# Arduino-Esplora-06.net
KiCad netlist of a schematic drawn in EAGLE
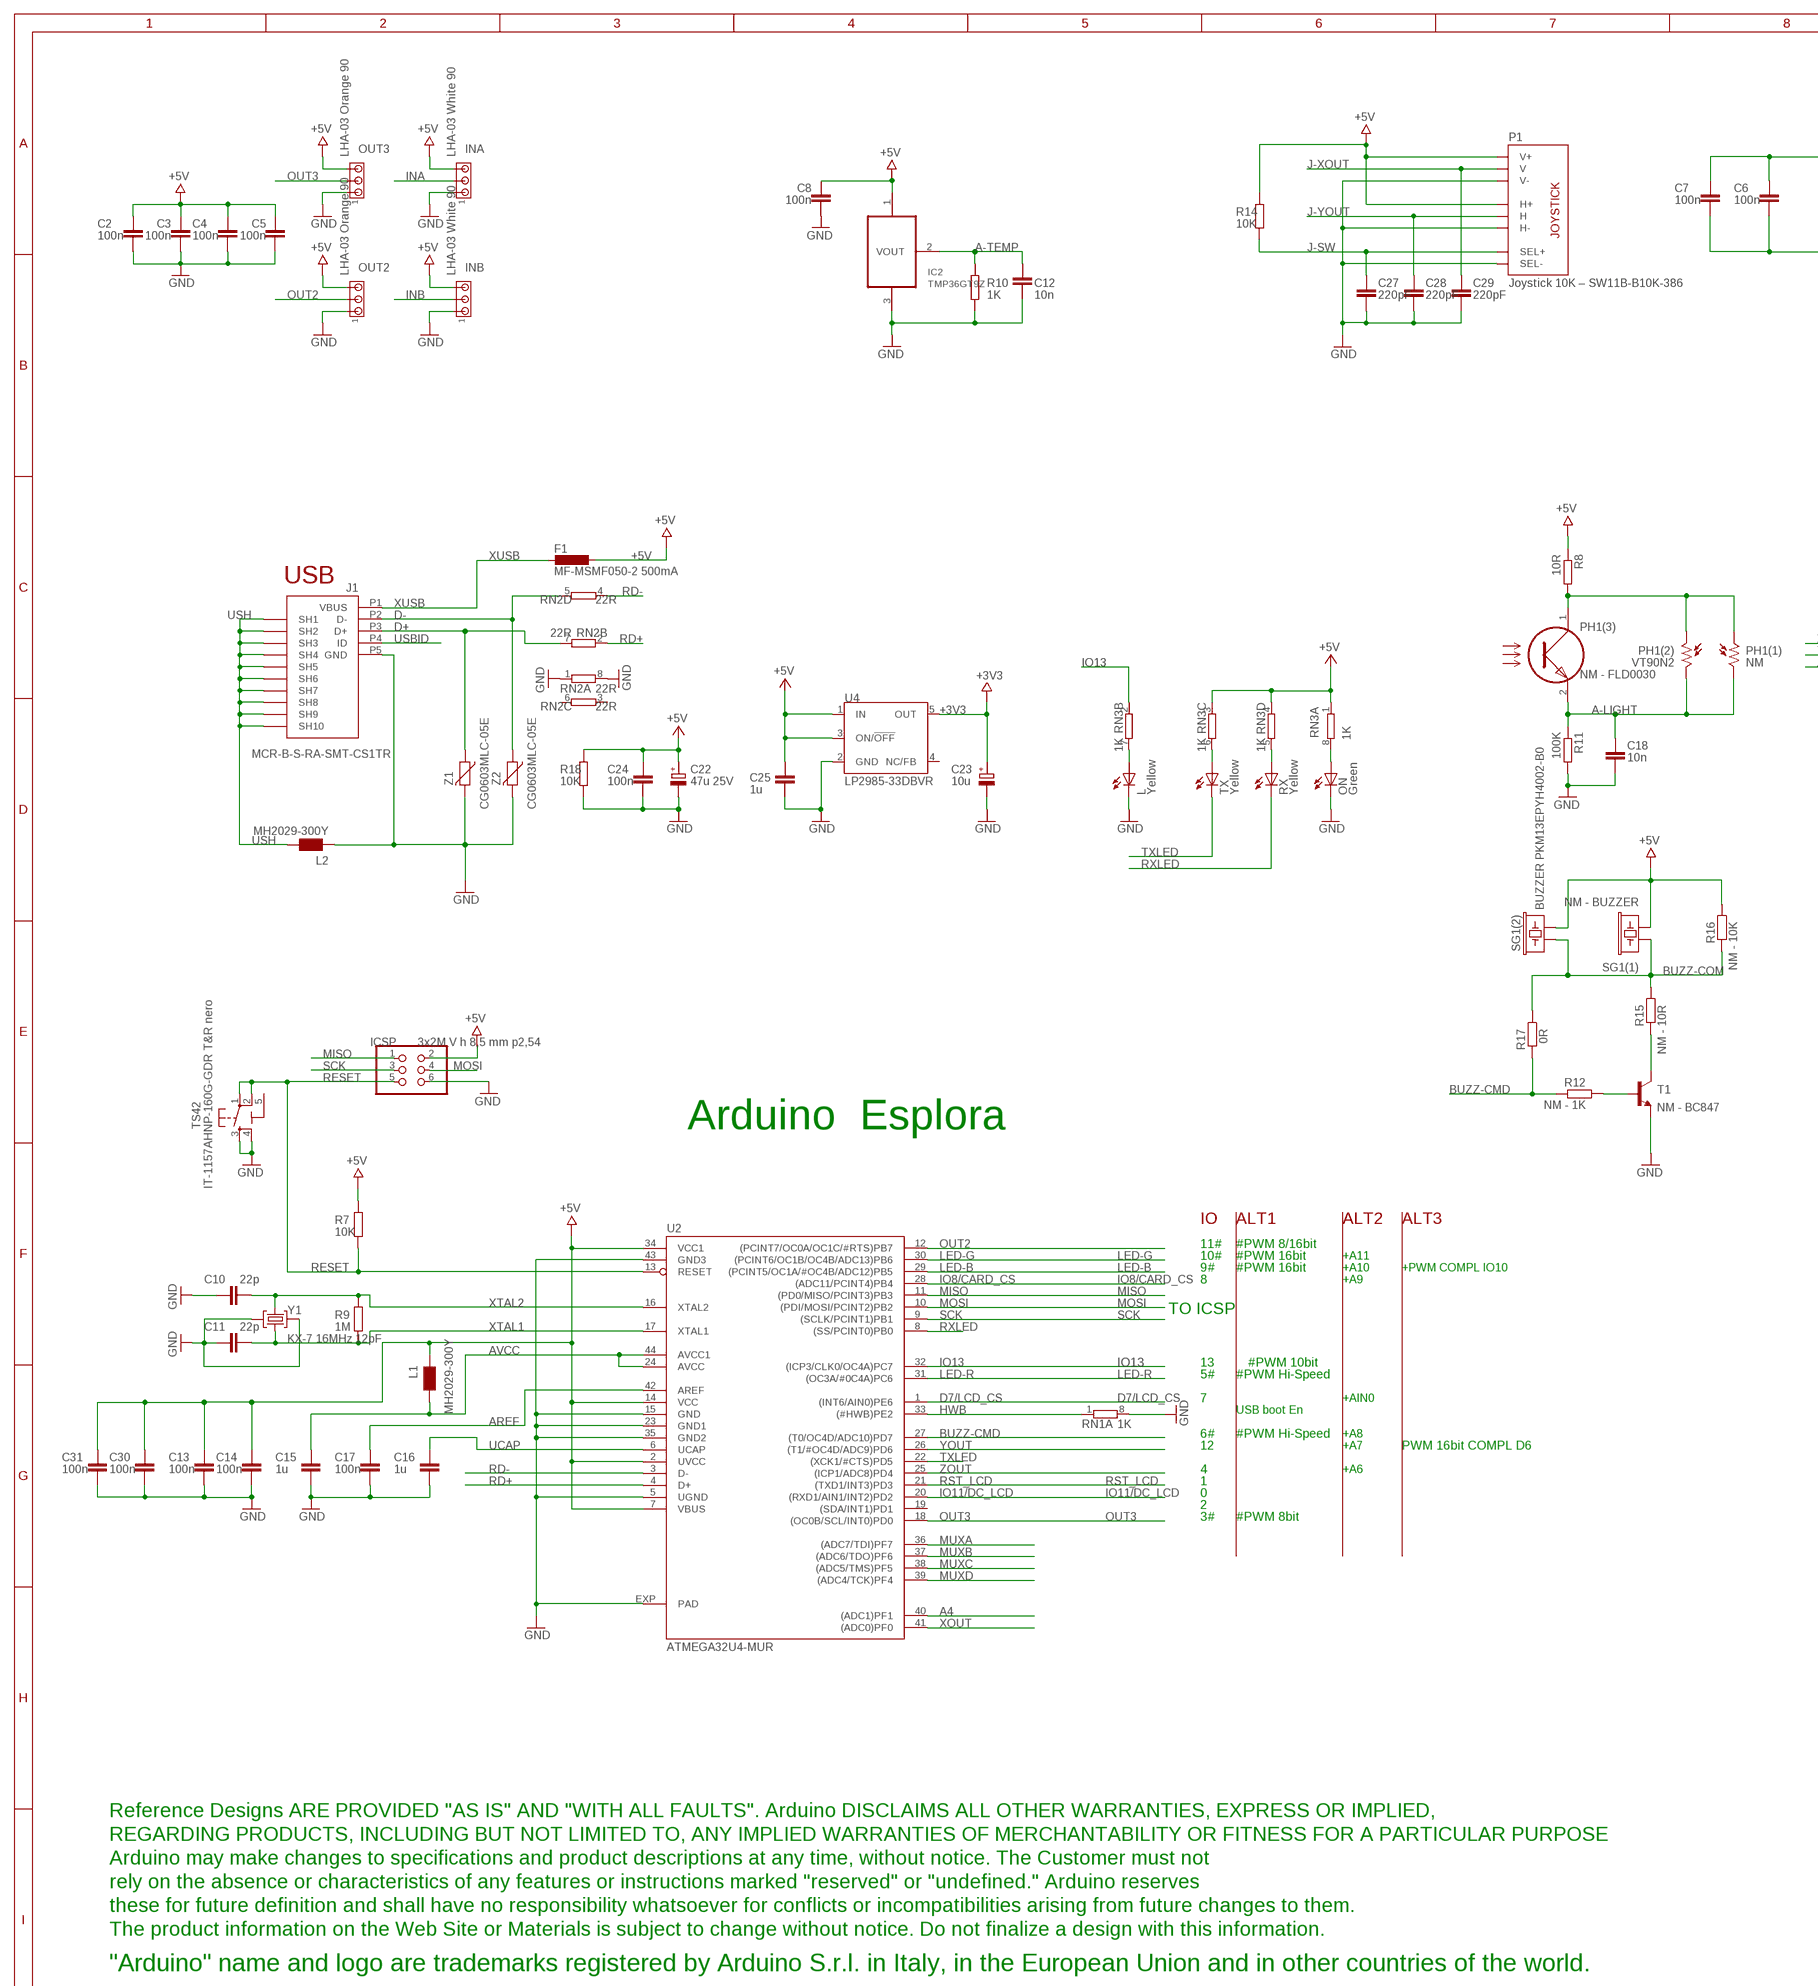
[diagram p0: schematic, sheet 1, part 1 of 2]
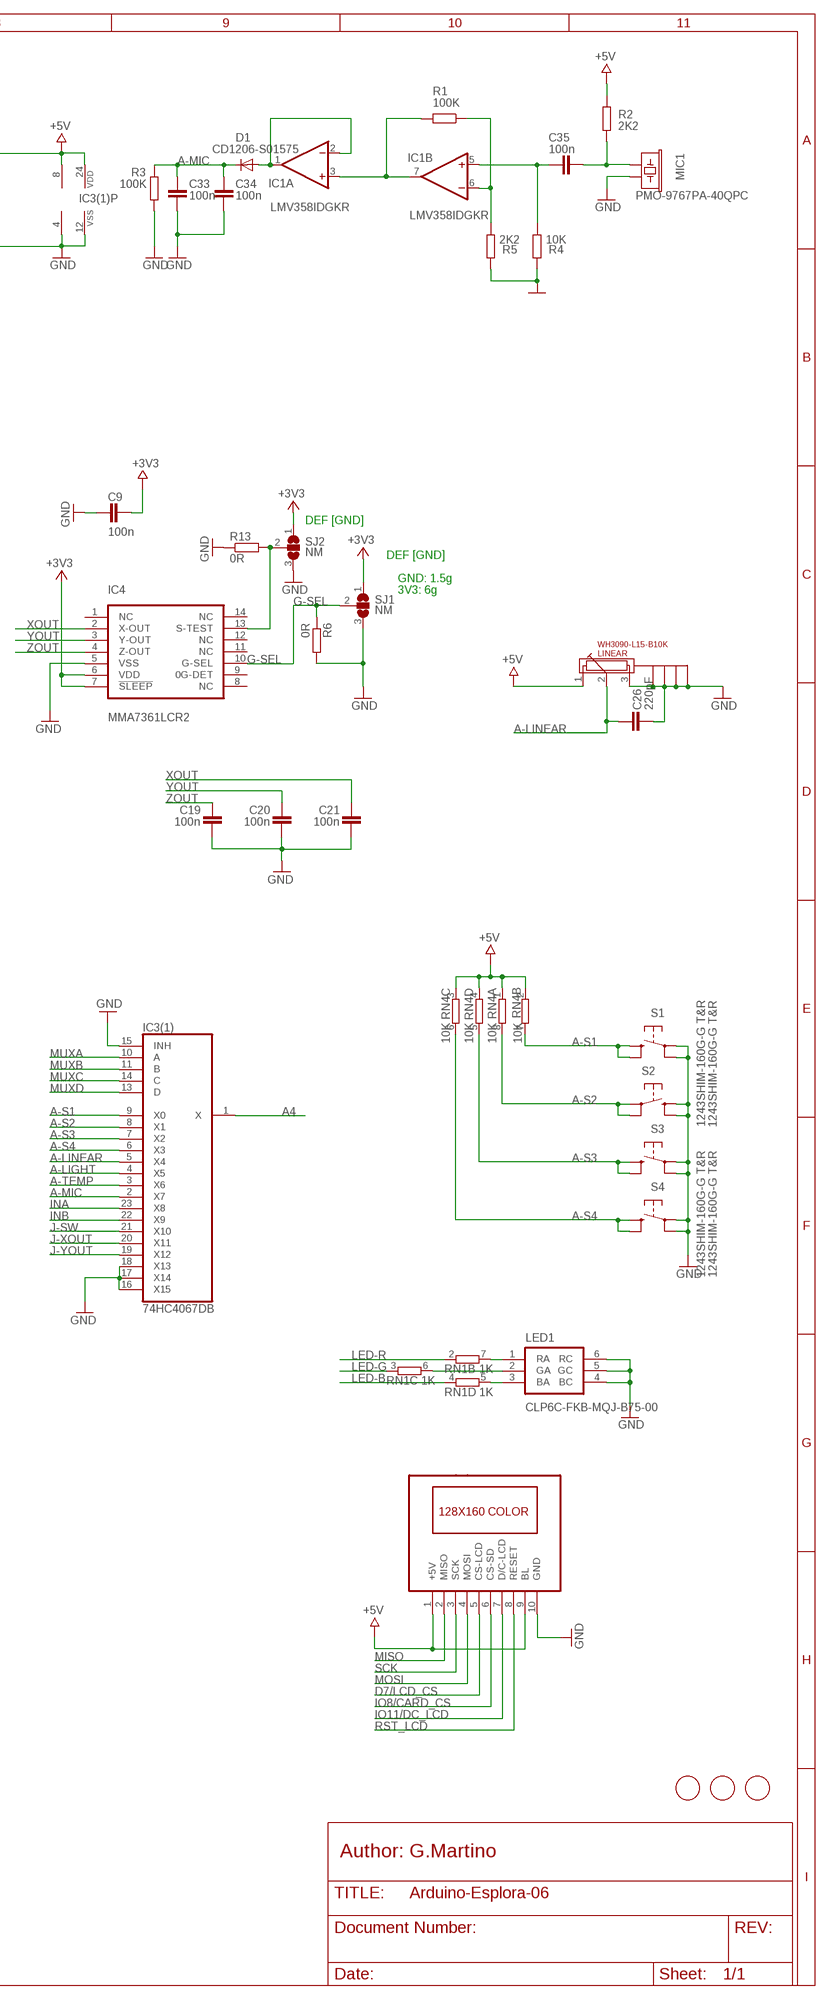
[diagram p1: schematic, sheet 1, part 2 of 2]

(export (version "E")
  (design (tool "Eeschema 10.0.6"))
  (components
    (comp (ref "C2")
      (value "100n")
      (footprint "eagle-import:C0603-ROUND")
      (libsource (lib "eagle-import") (part "C-EUC0603"))
    )
    (comp (ref "C3")
      (value "100n")
      (footprint "eagle-import:C0603-ROUND")
      (libsource (lib "eagle-import") (part "C-EUC0603"))
    )
    (comp (ref "C4")
      (value "100n")
      (footprint "eagle-import:C0603-ROUND")
      (libsource (lib "eagle-import") (part "C-EUC0603"))
    )
    (comp (ref "C5")
      (value "100n")
      (footprint "eagle-import:C0603-ROUND")
      (libsource (lib "eagle-import") (part "C-EUC0603"))
    )
    (comp (ref "C6")
      (value "100n")
      (footprint "eagle-import:C0603-ROUND")
      (libsource (lib "eagle-import") (part "C-EUC0603"))
    )
    (comp (ref "C7")
      (value "100n")
      (footprint "eagle-import:C0603-ROUND")
      (libsource (lib "eagle-import") (part "C-EUC0603"))
    )
    (comp (ref "C8")
      (value "100n")
      (footprint "eagle-import:C0603-ROUND")
      (libsource (lib "eagle-import") (part "C-EUC0603"))
    )
    (comp (ref "C9")
      (value "100n")
      (footprint "eagle-import:C0603-ROUND")
      (libsource (lib "eagle-import") (part "C-EUC0603"))
    )
    (comp (ref "C10")
      (value "22p")
      (footprint "eagle-import:C0603-ROUND")
      (libsource (lib "eagle-import") (part "C-EUC0603"))
    )
    (comp (ref "C11")
      (value "22p")
      (footprint "eagle-import:C0603-ROUND")
      (libsource (lib "eagle-import") (part "C-EUC0603"))
    )
    (comp (ref "C12")
      (value "10n")
      (footprint "eagle-import:C0603-ROUND")
      (libsource (lib "eagle-import") (part "C-EUC0603"))
    )
    (comp (ref "C13")
      (value "100n")
      (footprint "eagle-import:C0603-ROUND")
      (libsource (lib "eagle-import") (part "C-EUC0603"))
    )
    (comp (ref "C14")
      (value "100n")
      (footprint "eagle-import:C0603-ROUND")
      (libsource (lib "eagle-import") (part "C-EUC0603"))
    )
    (comp (ref "C15")
      (value "1u")
      (footprint "eagle-import:C0603-ROUND")
      (libsource (lib "eagle-import") (part "C-EUC0603"))
    )
    (comp (ref "C16")
      (value "1u")
      (footprint "eagle-import:C0603-ROUND")
      (libsource (lib "eagle-import") (part "C-EUC0603"))
    )
    (comp (ref "C17")
      (value "100n")
      (footprint "eagle-import:C0603-ROUND")
      (libsource (lib "eagle-import") (part "C-EUC0603"))
    )
    (comp (ref "C18")
      (value "10n")
      (footprint "eagle-import:C0603-ROUND")
      (libsource (lib "eagle-import") (part "C-EUC0603"))
    )
    (comp (ref "C19")
      (value "100n")
      (footprint "eagle-import:C0603-ROUND")
      (libsource (lib "eagle-import") (part "C-EUC0603"))
    )
    (comp (ref "C20")
      (value "100n")
      (footprint "eagle-import:C0603-ROUND")
      (libsource (lib "eagle-import") (part "C-EUC0603"))
    )
    (comp (ref "C21")
      (value "100n")
      (footprint "eagle-import:C0603-ROUND")
      (libsource (lib "eagle-import") (part "C-EUC0603"))
    )
    (comp (ref "C22")
      (value "47u 25V")
      (footprint "eagle-import:PANASONIC_D")
      (libsource (lib "eagle-import") (part "CPOL-EUD"))
    )
    (comp (ref "C23")
      (value "10u")
      (footprint "eagle-import:SMC_B")
      (libsource (lib "eagle-import") (part "CPOL-EUSMCB"))
    )
    (comp (ref "C24")
      (value "100n")
      (footprint "eagle-import:C0603-ROUND")
      (libsource (lib "eagle-import") (part "C-EUC0603"))
    )
    (comp (ref "C25")
      (value "1u")
      (footprint "eagle-import:C0603-ROUND")
      (libsource (lib "eagle-import") (part "C-EUC0603"))
    )
    (comp (ref "C26")
      (value "220pF")
      (footprint "eagle-import:C0603-ROUND")
      (libsource (lib "eagle-import") (part "C-EUC0603"))
    )
    (comp (ref "C27")
      (value "220pF")
      (footprint "eagle-import:C0603-ROUND")
      (libsource (lib "eagle-import") (part "C-EUC0603"))
    )
    (comp (ref "C28")
      (value "220pF")
      (footprint "eagle-import:C0603-ROUND")
      (libsource (lib "eagle-import") (part "C-EUC0603"))
    )
    (comp (ref "C29")
      (value "220pF")
      (footprint "eagle-import:C0603-ROUND")
      (libsource (lib "eagle-import") (part "C-EUC0603"))
    )
    (comp (ref "C30")
      (value "100n")
      (footprint "eagle-import:C0603-ROUND")
      (libsource (lib "eagle-import") (part "C-EUC0603"))
    )
    (comp (ref "C31")
      (value "100n")
      (footprint "eagle-import:C0603-ROUND")
      (libsource (lib "eagle-import") (part "C-EUC0603"))
    )
    (comp (ref "C33")
      (value "100n")
      (footprint "eagle-import:C0603-ROUND")
      (libsource (lib "eagle-import") (part "C-EUC0603"))
    )
    (comp (ref "C34")
      (value "100n")
      (footprint "eagle-import:C0603-ROUND")
      (libsource (lib "eagle-import") (part "C-EUC0603"))
    )
    (comp (ref "C35")
      (value "100n")
      (footprint "eagle-import:C0603-ROUND")
      (libsource (lib "eagle-import") (part "C-EUC0603"))
    )
    (comp (ref "D1")
      (value "CD1206-S01575")
      (footprint "eagle-import:MINIMELF")
      (libsource (lib "eagle-import") (part "DIODE-MINIMELF"))
    )
    (comp (ref "F1")
      (value "MF-MSMF050-2 500mA")
      (footprint "eagle-import:L1812")
      (libsource (lib "eagle-import") (part "L-EUL1812"))
    )
    (comp (ref "FID1")
      (value "FIDUCIALMOUNT")
      (footprint "eagle-import:FIDUCIA-MOUNT")
      (libsource (lib "eagle-import") (part "FIDUCIALMOUNT"))
    )
    (comp (ref "FID2")
      (value "FIDUCIALMOUNT")
      (footprint "eagle-import:FIDUCIA-MOUNT")
      (libsource (lib "eagle-import") (part "FIDUCIALMOUNT"))
    )
    (comp (ref "FID3")
      (value "FIDUCIALMOUNT")
      (footprint "eagle-import:FIDUCIA-MOUNT")
      (libsource (lib "eagle-import") (part "FIDUCIALMOUNT"))
    )
    (comp (ref "IC1")
      (value "LMV358IDGKR")
      (footprint "eagle-import:MSOP08")
      (libsource (lib "eagle-import") (part "LMV358?MMX"))
    )
    (comp (ref "IC2")
      (value "TMP36GT9Z")
      (footprint "eagle-import:TO92")
      (libsource (lib "eagle-import") (part "LM35TO-92"))
    )
    (comp (ref "IC3(1)")
      (value "74HC4067DB")
      (footprint "eagle-import:SSOP24(0.65)")
      (libsource (lib "eagle-import") (part "4067SM96"))
    )
    (comp (ref "IC4")
      (value "MMA7361LCR2")
      (footprint "eagle-import:LGA-14_3X5_0.8")
      (libsource (lib "eagle-import") (part "MMA7361LC"))
    )
    (comp (ref "ICSP")
      (value "3x2M V h 8,5 mm p2,54")
      (footprint "eagle-import:2X03")
      (libsource (lib "eagle-import") (part "PINHD-2X3"))
    )
    (comp (ref "INA")
      (value "LHA-03 White 90")
      (footprint "eagle-import:10X03MTA")
      (libsource (lib "eagle-import") (part "MTA03-100"))
    )
    (comp (ref "INB")
      (value "LHA-03 White 90")
      (footprint "eagle-import:10X03MTA")
      (libsource (lib "eagle-import") (part "MTA03-100"))
    )
    (comp (ref "J1")
      (value "MCR-B-S-RA-SMT-CS1TR")
      (footprint "eagle-import:CON2_USB_MICRO_B_AT")
      (libsource (lib "eagle-import") (part "MYCON2_USB-MINI-B"))
    )
    (comp (ref "L")
      (value "Yellow")
      (footprint "eagle-import:CHIPLED_0805")
      (libsource (lib "eagle-import") (part "LEDCHIPLED_0805"))
    )
    (comp (ref "L1")
      (value "MH2029-300Y")
      (footprint "eagle-import:0805")
      (libsource (lib "eagle-import") (part "WE-CBF_0805"))
    )
    (comp (ref "L2")
      (value "MH2029-300Y")
      (footprint "eagle-import:0805")
      (libsource (lib "eagle-import") (part "WE-CBF_0805"))
    )
    (comp (ref "LCD1")
      (value "LCD1")
      (footprint "eagle-import:1.8'_LCD-LCD-TFT(128X160)")
      (libsource (lib "eagle-import") (part "1.8'_LCD-TFT(128X160)+SD-CARD"))
    )
    (comp (ref "LED1")
      (value "CLP6C-FKB-MQJ-B75-00")
      (footprint "eagle-import:RGB-LED")
      (libsource (lib "eagle-import") (part "RGB-LED"))
    )
    (comp (ref "LINEAR")
      (value "WH3090-L15-B10K")
      (footprint "eagle-import:RA3021-202")
      (libsource (lib "eagle-import") (part "RA3021-202"))
    )
    (comp (ref "MIC1")
      (value "PMO-9767PA-40QPC")
      (footprint "eagle-import:MIC-9.7MM")
      (libsource (lib "eagle-import") (part "MIC9.7MM"))
    )
    (comp (ref "ON")
      (value "Green")
      (footprint "eagle-import:CHIPLED_0805")
      (libsource (lib "eagle-import") (part "LEDCHIPLED_0805"))
    )
    (comp (ref "OUT2")
      (value "LHA-03 Orange 90")
      (footprint "eagle-import:10X03MTA")
      (libsource (lib "eagle-import") (part "MTA03-100"))
    )
    (comp (ref "OUT3")
      (value "LHA-03 Orange 90")
      (footprint "eagle-import:10X03MTA")
      (libsource (lib "eagle-import") (part "MTA03-100"))
    )
    (comp (ref "P1")
      (value "Joystick 10K – SW11B-B10K-386")
      (footprint "eagle-import:ALP_JOYSTICK")
      (libsource (lib "eagle-import") (part "ALP_JOYSTICKPTH"))
    )
    (comp (ref "PH1(1)")
      (value "NM")
      (footprint "eagle-import:T0-46-A10XX")
      (libsource (lib "eagle-import") (part "A1050_09"))
    )
    (comp (ref "PH1(2)")
      (value "VT90N2")
      (footprint "eagle-import:TO-8_B10")
      (libsource (lib "eagle-import") (part "?1060B_23"))
    )
    (comp (ref "PH1(3)")
      (value "NM - FLD0030")
      (footprint "eagle-import:FLD00030")
      (libsource (lib "eagle-import") (part "FLD00030"))
    )
    (comp (ref "R1")
      (value "100K")
      (footprint "eagle-import:R0603-ROUND")
      (libsource (lib "eagle-import") (part "R-EU_R0603"))
    )
    (comp (ref "R2")
      (value "2K2")
      (footprint "eagle-import:R0603-ROUND")
      (libsource (lib "eagle-import") (part "R-EU_R0603"))
    )
    (comp (ref "R3")
      (value "100K")
      (footprint "eagle-import:R0603-ROUND")
      (libsource (lib "eagle-import") (part "R-EU_R0603"))
    )
    (comp (ref "R4")
      (value "10K")
      (footprint "eagle-import:R0603-ROUND")
      (libsource (lib "eagle-import") (part "R-EU_R0603"))
    )
    (comp (ref "R5")
      (value "2K2")
      (footprint "eagle-import:R0603-ROUND")
      (libsource (lib "eagle-import") (part "R-EU_R0603"))
    )
    (comp (ref "R6")
      (value "0R")
      (footprint "eagle-import:R0603-ROUND")
      (libsource (lib "eagle-import") (part "R-EU_R0603"))
    )
    (comp (ref "R7")
      (value "10K")
      (footprint "eagle-import:R0603-ROUND")
      (libsource (lib "eagle-import") (part "R-EU_R0603"))
    )
    (comp (ref "R8")
      (value "10R")
      (footprint "eagle-import:R0603-ROUND")
      (libsource (lib "eagle-import") (part "R-EU_R0603"))
    )
    (comp (ref "R9")
      (value "1M")
      (footprint "eagle-import:R0603-ROUND")
      (libsource (lib "eagle-import") (part "R-EU_R0603"))
    )
    (comp (ref "R10")
      (value "1K")
      (footprint "eagle-import:R0603-ROUND")
      (libsource (lib "eagle-import") (part "R-EU_R0603"))
    )
    (comp (ref "R11")
      (value "100K")
      (footprint "eagle-import:R0603-ROUND")
      (libsource (lib "eagle-import") (part "R-EU_R0603"))
    )
    (comp (ref "R12")
      (value "NM - 1K")
      (footprint "eagle-import:R0603-ROUND")
      (libsource (lib "eagle-import") (part "R-EU_R0603"))
    )
    (comp (ref "R13")
      (value "0R")
      (footprint "eagle-import:R0603-ROUND")
      (libsource (lib "eagle-import") (part "R-EU_R0603"))
    )
    (comp (ref "R14")
      (value "10K")
      (footprint "eagle-import:R0603-ROUND")
      (libsource (lib "eagle-import") (part "R-EU_R0603"))
    )
    (comp (ref "R15")
      (value "NM - 10R")
      (footprint "eagle-import:R0603-ROUND")
      (libsource (lib "eagle-import") (part "R-EU_R0603"))
    )
    (comp (ref "R16")
      (value "NM - 10K")
      (footprint "eagle-import:R0603-ROUND")
      (libsource (lib "eagle-import") (part "R-EU_R0603"))
    )
    (comp (ref "R17")
      (value "0R")
      (footprint "eagle-import:R0603-ROUND")
      (libsource (lib "eagle-import") (part "R-EU_R0603"))
    )
    (comp (ref "R18")
      (value "10K")
      (footprint "eagle-import:R0603-ROUND")
      (libsource (lib "eagle-import") (part "R-EU_R0603"))
    )
    (comp (ref "RN1")
      (value "1K")
      (footprint "eagle-import:CAY16")
      (libsource (lib "eagle-import") (part "4R-NCAY16"))
    )
    (comp (ref "RN2")
      (value "22R")
      (footprint "eagle-import:CAY16")
      (libsource (lib "eagle-import") (part "4R-NCAY16"))
    )
    (comp (ref "RN3")
      (value "1K")
      (footprint "eagle-import:CAY16")
      (libsource (lib "eagle-import") (part "4R-NCAY16"))
    )
    (comp (ref "RN4")
      (value "10K")
      (footprint "eagle-import:CAY16")
      (libsource (lib "eagle-import") (part "4R-NCAY16"))
    )
    (comp (ref "RX")
      (value "Yellow")
      (footprint "eagle-import:CHIPLED_0805")
      (libsource (lib "eagle-import") (part "LEDCHIPLED_0805"))
    )
    (comp (ref "S1")
      (value "1243SHIM-160G-G T&R")
      (footprint "eagle-import:TACTILE-SMD-12MM")
      (libsource (lib "eagle-import") (part "TACTILE_SWITCHTACTILE_SWITCH_SMD-12MM"))
    )
    (comp (ref "S2")
      (value "1243SHIM-160G-G T&R")
      (footprint "eagle-import:TACTILE-SMD-12MM")
      (libsource (lib "eagle-import") (part "TACTILE_SWITCHTACTILE_SWITCH_SMD-12MM"))
    )
    (comp (ref "S3")
      (value "1243SHIM-160G-G T&R")
      (footprint "eagle-import:TACTILE-SMD-12MM")
      (libsource (lib "eagle-import") (part "TACTILE_SWITCHTACTILE_SWITCH_SMD-12MM"))
    )
    (comp (ref "S4")
      (value "1243SHIM-160G-G T&R")
      (footprint "eagle-import:TACTILE-SMD-12MM")
      (libsource (lib "eagle-import") (part "TACTILE_SWITCHTACTILE_SWITCH_SMD-12MM"))
    )
    (comp (ref "SG1(1)")
      (value "NM - BUZZER")
      (footprint "eagle-import:BUZZER-12MM-NS-P5MM")
      (libsource (lib "eagle-import") (part "BUZZER1NS"))
    )
    (comp (ref "SG1(2)")
      (value "BUZZER PKM13EPYH4002-B0")
      (footprint "eagle-import:BUZZER-12MM-NS-KIT")
      (libsource (lib "eagle-import") (part "BUZZER1PTH-NS-KIT"))
    )
    (comp (ref "SJ1")
      (value "NM")
      (footprint "eagle-import:SJ_2")
      (libsource (lib "eagle-import") (part "SJ2W"))
    )
    (comp (ref "SJ2")
      (value "NM")
      (footprint "eagle-import:SJ_2")
      (libsource (lib "eagle-import") (part "SJ2W"))
    )
    (comp (ref "T1")
      (value "NM - BC847")
      (footprint "eagle-import:SOT23")
      (libsource (lib "eagle-import") (part "BC847"))
    )
    (comp (ref "TS42")
      (value "IT-1157AHNP-160G-GDR T&R nero")
      (footprint "eagle-import:TS42")
      (libsource (lib "eagle-import") (part "TS42"))
    )
    (comp (ref "TX")
      (value "Yellow")
      (footprint "eagle-import:CHIPLED_0805")
      (libsource (lib "eagle-import") (part "LEDCHIPLED_0805"))
    )
    (comp (ref "U$19")
      (value "DISCLAIMER")
      (footprint "eagle-import:DISCLAIMER")
      (libsource (lib "eagle-import") (part "DISCLAIMER"))
    )
    (comp (ref "U2")
      (value "ATMEGA32U4-MUR")
      (footprint "eagle-import:QFN44ML7X7")
      (libsource (lib "eagle-import") (part "ATMEGA32U4-MU"))
    )
    (comp (ref "U4")
      (value "LP2985-33DBVR")
      (footprint "eagle-import:SOT23-DBV")
      (libsource (lib "eagle-import") (part "LP2985-XXDBVR33"))
    )
    (comp (ref "Y1")
      (value "KX-7 16MHz 12pF")
      (footprint "eagle-import:CRYSTAL-3.2-2.5")
      (libsource (lib "eagle-import") (part "CRYSTAL-3.2-2.5"))
    )
    (comp (ref "Z1")
      (value "CG0603MLC-05E")
      (footprint "eagle-import:CT_CN0603")
      (libsource (lib "eagle-import") (part "VARISTORCN0603"))
    )
    (comp (ref "Z2")
      (value "CG0603MLC-05E")
      (footprint "eagle-import:CT_CN0603")
      (libsource (lib "eagle-import") (part "VARISTORCN0603"))
    )
  )
  (nets
    (net (code "1") (name "+3V3") (class "Default")
      (node (ref "C23") (pin "+") (pinfunction "+_+") (pintype "passive"))
      (node (ref "C9") (pin "2") (pinfunction "2_2") (pintype "passive"))
      (node (ref "IC4") (pin "6") (pinfunction "VDD_6") (pintype "power_in"))
      (node (ref "IC4") (pin "7") (pinfunction "~{SLEEP}_7") (pintype "input"))
      (node (ref "SJ1") (pin "1") (pinfunction "1_1") (pintype "passive"))
      (node (ref "SJ2") (pin "1") (pinfunction "1_1") (pintype "passive"))
      (node (ref "U4") (pin "5") (pinfunction "OUT_5") (pintype "passive"))
    )
    (net (code "2") (name "+5V") (class "Default")
      (node (ref "C13") (pin "1") (pinfunction "1_1") (pintype "passive"))
      (node (ref "C14") (pin "1") (pinfunction "1_1") (pintype "passive"))
      (node (ref "C2") (pin "2") (pinfunction "2_2") (pintype "passive"))
      (node (ref "C22") (pin "+") (pinfunction "+_+") (pintype "passive"))
      (node (ref "C24") (pin "2") (pinfunction "2_2") (pintype "passive"))
      (node (ref "C25") (pin "2") (pinfunction "2_2") (pintype "passive"))
      (node (ref "C3") (pin "2") (pinfunction "2_2") (pintype "passive"))
      (node (ref "C30") (pin "1") (pinfunction "1_1") (pintype "passive"))
      (node (ref "C31") (pin "1") (pinfunction "1_1") (pintype "passive"))
      (node (ref "C4") (pin "2") (pinfunction "2_2") (pintype "passive"))
      (node (ref "C5") (pin "2") (pinfunction "2_2") (pintype "passive"))
      (node (ref "C6") (pin "2") (pinfunction "2_2") (pintype "passive"))
      (node (ref "C7") (pin "2") (pinfunction "2_2") (pintype "passive"))
      (node (ref "C8") (pin "2") (pinfunction "2_2") (pintype "passive"))
      (node (ref "F1") (pin "1") (pinfunction "1_1") (pintype "passive"))
      (node (ref "IC1") (pin "8") (pinfunction "V+_8") (pintype "power_in"))
      (node (ref "IC2") (pin "1") (pinfunction "+VS_1") (pintype "power_in"))
      (node (ref "IC3(1)") (pin "24") (pinfunction "VDD_24") (pintype "power_in"))
      (node (ref "ICSP") (pin "2") (pinfunction "2_2") (pintype "passive"))
      (node (ref "INA") (pin "3") (pinfunction "3_3") (pintype "passive"))
      (node (ref "INB") (pin "3") (pinfunction "3_3") (pintype "passive"))
      (node (ref "L1") (pin "1") (pinfunction "1_1") (pintype "passive"))
      (node (ref "LCD1") (pin "1") (pinfunction "+5V_1") (pintype "power_in"))
      (node (ref "LCD1") (pin "9") (pinfunction "BL_9") (pintype "input"))
      (node (ref "LINEAR") (pin "1") (pinfunction "1_1") (pintype "bidirectional"))
      (node (ref "OUT2") (pin "3") (pinfunction "3_3") (pintype "passive"))
      (node (ref "OUT3") (pin "3") (pinfunction "3_3") (pintype "passive"))
      (node (ref "P1") (pin "H1") (pinfunction "H+_H1") (pintype "bidirectional"))
      (node (ref "P1") (pin "V1") (pinfunction "V+_V1") (pintype "bidirectional"))
      (node (ref "R14") (pin "1") (pinfunction "1_1") (pintype "passive"))
      (node (ref "R16") (pin "1") (pinfunction "1_1") (pintype "passive"))
      (node (ref "R18") (pin "1") (pinfunction "1_1") (pintype "passive"))
      (node (ref "R2") (pin "1") (pinfunction "1_1") (pintype "passive"))
      (node (ref "R7") (pin "1") (pinfunction "1_1") (pintype "passive"))
      (node (ref "R8") (pin "1") (pinfunction "1_1") (pintype "passive"))
      (node (ref "RN3") (pin "1") (pinfunction "1_1") (pintype "passive"))
      (node (ref "RN3") (pin "3") (pinfunction "1_3") (pintype "passive"))
      (node (ref "RN3") (pin "4") (pinfunction "1_4") (pintype "passive"))
      (node (ref "RN4") (pin "1") (pinfunction "1_1") (pintype "passive"))
      (node (ref "RN4") (pin "2") (pinfunction "1_2") (pintype "passive"))
      (node (ref "RN4") (pin "3") (pinfunction "1_3") (pintype "passive"))
      (node (ref "RN4") (pin "4") (pinfunction "1_4") (pintype "passive"))
      (node (ref "SG1(1)") (pin "-") (pinfunction "2_-") (pintype "passive"))
      (node (ref "SG1(2)") (pin "-") (pinfunction "2_-") (pintype "passive"))
      (node (ref "U2") (pin "14") (pinfunction "VCC_14") (pintype "power_in"))
      (node (ref "U2") (pin "2") (pinfunction "UVCC_2") (pintype "power_in"))
      (node (ref "U2") (pin "34") (pinfunction "VCC1_34") (pintype "power_in"))
      (node (ref "U2") (pin "7") (pinfunction "VBUS_7") (pintype "input"))
      (node (ref "U4") (pin "1") (pinfunction "IN_1") (pintype "input"))
      (node (ref "U4") (pin "3") (pinfunction "ON/~{OFF}_3") (pintype "input"))
    )
    (net (code "3") (name "/5-GND") (class "Default")
      (node (ref "TS42") (pin "5") (pinfunction "5-GND_5") (pintype "power_in"))
    )
    (net (code "4") (name "/A-LIGHT") (class "Default")
      (node (ref "C18") (pin "2") (pinfunction "2_2") (pintype "passive"))
      (node (ref "IC3(1)") (pin "4") (pinfunction "X5_4") (pintype "input"))
      (node (ref "PH1(1)") (pin "2") (pinfunction "2_2") (pintype "passive"))
      (node (ref "PH1(2)") (pin "2") (pinfunction "2_2") (pintype "passive"))
      (node (ref "PH1(3)") (pin "2") (pinfunction "2_2") (pintype "bidirectional"))
      (node (ref "R11") (pin "1") (pinfunction "1_1") (pintype "passive"))
    )
    (net (code "5") (name "/A-LINEAR") (class "Default")
      (node (ref "C26") (pin "2") (pinfunction "2_2") (pintype "passive"))
      (node (ref "IC3(1)") (pin "5") (pinfunction "X4_5") (pintype "input"))
      (node (ref "LINEAR") (pin "2") (pinfunction "2_2") (pintype "bidirectional"))
    )
    (net (code "6") (name "/A-MIC") (class "Default")
      (node (ref "C33") (pin "2") (pinfunction "2_2") (pintype "passive"))
      (node (ref "C34") (pin "2") (pinfunction "2_2") (pintype "passive"))
      (node (ref "D1") (pin "C") (pinfunction "C_C") (pintype "passive"))
      (node (ref "IC3(1)") (pin "2") (pinfunction "X7_2") (pintype "input"))
      (node (ref "R3") (pin "1") (pinfunction "1_1") (pintype "passive"))
    )
    (net (code "7") (name "/A-S1") (class "Default")
      (node (ref "IC3(1)") (pin "9") (pinfunction "X0_9") (pintype "input"))
      (node (ref "RN4") (pin "7") (pinfunction "2_7") (pintype "passive"))
      (node (ref "S1") (pin "P$3") (pinfunction "3_P$3") (pintype "passive"))
      (node (ref "S1") (pin "P$4") (pinfunction "4_P$4") (pintype "passive"))
    )
    (net (code "8") (name "/A-S2") (class "Default")
      (node (ref "IC3(1)") (pin "8") (pinfunction "X1_8") (pintype "input"))
      (node (ref "RN4") (pin "8") (pinfunction "2_8") (pintype "passive"))
      (node (ref "S2") (pin "P$1") (pinfunction "1_P$1") (pintype "passive"))
      (node (ref "S2") (pin "P$2") (pinfunction "2_P$2") (pintype "passive"))
    )
    (net (code "9") (name "/A-S3") (class "Default")
      (node (ref "IC3(1)") (pin "7") (pinfunction "X2_7") (pintype "input"))
      (node (ref "RN4") (pin "5") (pinfunction "2_5") (pintype "passive"))
      (node (ref "S3") (pin "P$3") (pinfunction "3_P$3") (pintype "passive"))
      (node (ref "S3") (pin "P$4") (pinfunction "4_P$4") (pintype "passive"))
    )
    (net (code "10") (name "/A-S4") (class "Default")
      (node (ref "IC3(1)") (pin "6") (pinfunction "X3_6") (pintype "input"))
      (node (ref "RN4") (pin "6") (pinfunction "2_6") (pintype "passive"))
      (node (ref "S4") (pin "P$3") (pinfunction "3_P$3") (pintype "passive"))
      (node (ref "S4") (pin "P$4") (pinfunction "4_P$4") (pintype "passive"))
    )
    (net (code "11") (name "/A-TEMP") (class "Default")
      (node (ref "C12") (pin "2") (pinfunction "2_2") (pintype "passive"))
      (node (ref "IC2") (pin "2") (pinfunction "VOUT_2") (pintype "output"))
      (node (ref "IC3(1)") (pin "3") (pinfunction "X6_3") (pintype "input"))
      (node (ref "R10") (pin "1") (pinfunction "1_1") (pintype "passive"))
    )
    (net (code "12") (name "/A4") (class "Default")
      (node (ref "IC3(1)") (pin "1") (pinfunction "X_1") (pintype "output"))
      (node (ref "U2") (pin "40") (pinfunction "(ADC1)PF1_40") (pintype "bidirectional"))
    )
    (net (code "13") (name "/AREF") (class "Default")
      (node (ref "C17") (pin "2") (pinfunction "2_2") (pintype "passive"))
      (node (ref "U2") (pin "42") (pinfunction "AREF_42") (pintype "power_in"))
    )
    (net (code "14") (name "/AVCC") (class "Default")
      (node (ref "C15") (pin "1") (pinfunction "1_1") (pintype "passive"))
      (node (ref "L1") (pin "2") (pinfunction "2_2") (pintype "passive"))
      (node (ref "U2") (pin "24") (pinfunction "AVCC_24") (pintype "power_in"))
      (node (ref "U2") (pin "44") (pinfunction "AVCC1_44") (pintype "power_in"))
    )
    (net (code "15") (name "/BUZZ-CMD") (class "Default")
      (node (ref "R12") (pin "2") (pinfunction "2_2") (pintype "passive"))
      (node (ref "R17") (pin "2") (pinfunction "2_2") (pintype "passive"))
      (node (ref "U2") (pin "27") (pinfunction "(T0/OC4D/ADC10)PD7_27") (pintype "bidirectional"))
    )
    (net (code "16") (name "/BUZZ-COM") (class "Default")
      (node (ref "R15") (pin "1") (pinfunction "1_1") (pintype "passive"))
      (node (ref "R16") (pin "2") (pinfunction "2_2") (pintype "passive"))
      (node (ref "R17") (pin "1") (pinfunction "1_1") (pintype "passive"))
      (node (ref "SG1(1)") (pin "+") (pinfunction "1_+") (pintype "passive"))
      (node (ref "SG1(2)") (pin "+") (pinfunction "1_+") (pintype "passive"))
    )
    (net (code "17") (name "/D+") (class "Default")
      (node (ref "J1") (pin "P3") (pinfunction "D+_P3") (pintype "bidirectional"))
      (node (ref "RN2") (pin "7") (pinfunction "2_7") (pintype "passive"))
      (node (ref "Z1") (pin "1") (pinfunction "1_1") (pintype "passive"))
    )
    (net (code "18") (name "/D-") (class "Default")
      (node (ref "J1") (pin "P2") (pinfunction "D-_P2") (pintype "bidirectional"))
      (node (ref "RN2") (pin "5") (pinfunction "2_5") (pintype "passive"))
      (node (ref "Z2") (pin "1") (pinfunction "1_1") (pintype "passive"))
    )
    (net (code "19") (name "/D7{slash}LCD_CS") (class "Default")
      (node (ref "LCD1") (pin "5") (pinfunction "CS-LCD_5") (pintype "input"))
      (node (ref "U2") (pin "1") (pinfunction "(INT6/AIN0)PE6_1") (pintype "bidirectional"))
    )
    (net (code "20") (name "/G-SEL") (class "Default")
      (node (ref "IC4") (pin "10") (pinfunction "G-SEL_10") (pintype "input"))
      (node (ref "R6") (pin "1") (pinfunction "1_1") (pintype "passive"))
      (node (ref "SJ1") (pin "2") (pinfunction "2_2") (pintype "passive"))
    )
    (net (code "21") (name "/HWB") (class "Default")
      (node (ref "RN1") (pin "1") (pinfunction "1_1") (pintype "passive"))
      (node (ref "U2") (pin "33") (pinfunction "(#HWB)PE2_33") (pintype "bidirectional"))
    )
    (net (code "22") (name "/INA") (class "Default")
      (node (ref "IC3(1)") (pin "23") (pinfunction "X8_23") (pintype "input"))
      (node (ref "INA") (pin "2") (pinfunction "2_2") (pintype "passive"))
    )
    (net (code "23") (name "/INB") (class "Default")
      (node (ref "IC3(1)") (pin "22") (pinfunction "X9_22") (pintype "input"))
      (node (ref "INB") (pin "2") (pinfunction "2_2") (pintype "passive"))
    )
    (net (code "24") (name "/IO8{slash}CARD_CS") (class "Default")
      (node (ref "LCD1") (pin "6") (pinfunction "CS-SD_6") (pintype "input"))
      (node (ref "U2") (pin "28") (pinfunction "(ADC11/PCINT4)PB4_28") (pintype "bidirectional"))
    )
    (net (code "25") (name "/IO11{slash}DC_LCD") (class "Default")
      (node (ref "LCD1") (pin "7") (pinfunction "D/C-LCD_7") (pintype "bidirectional"))
      (node (ref "U2") (pin "20") (pinfunction "(RXD1/AIN1/INT2)PD2_20") (pintype "bidirectional"))
    )
    (net (code "26") (name "/IO13") (class "Default")
      (node (ref "RN3") (pin "2") (pinfunction "1_2") (pintype "passive"))
      (node (ref "U2") (pin "32") (pinfunction "(ICP3/CLK0/OC4A)PC7_32") (pintype "bidirectional"))
    )
    (net (code "27") (name "/J-SW") (class "Default")
      (node (ref "C27") (pin "2") (pinfunction "2_2") (pintype "passive"))
      (node (ref "IC3(1)") (pin "21") (pinfunction "X10_21") (pintype "input"))
      (node (ref "P1") (pin "B1A") (pinfunction "SEL+_B1A") (pintype "bidirectional"))
      (node (ref "R14") (pin "2") (pinfunction "2_2") (pintype "passive"))
    )
    (net (code "28") (name "/J-XOUT") (class "Default")
      (node (ref "C29") (pin "2") (pinfunction "2_2") (pintype "passive"))
      (node (ref "IC3(1)") (pin "20") (pinfunction "X11_20") (pintype "input"))
      (node (ref "P1") (pin "V2") (pinfunction "V_V2") (pintype "bidirectional"))
    )
    (net (code "29") (name "/J-YOUT") (class "Default")
      (node (ref "C28") (pin "2") (pinfunction "2_2") (pintype "passive"))
      (node (ref "IC3(1)") (pin "19") (pinfunction "X12_19") (pintype "input"))
      (node (ref "P1") (pin "H2") (pinfunction "H_H2") (pintype "bidirectional"))
    )
    (net (code "30") (name "/LED-B") (class "Default")
      (node (ref "RN1") (pin "4") (pinfunction "1_4") (pintype "passive"))
      (node (ref "U2") (pin "29") (pinfunction "(PCINT5/OC1A/#OC4B/ADC12)PB5_29") (pintype "bidirectional"))
    )
    (net (code "31") (name "/LED-G") (class "Default")
      (node (ref "RN1") (pin "3") (pinfunction "1_3") (pintype "passive"))
      (node (ref "U2") (pin "30") (pinfunction "(PCINT6/OC1B/OC4B/ADC13)PB6_30") (pintype "bidirectional"))
    )
    (net (code "32") (name "/LED-R") (class "Default")
      (node (ref "RN1") (pin "2") (pinfunction "1_2") (pintype "passive"))
      (node (ref "U2") (pin "31") (pinfunction "(OC3A/#0C4A)PC6_31") (pintype "bidirectional"))
    )
    (net (code "33") (name "/MISO") (class "Default")
      (node (ref "ICSP") (pin "1") (pinfunction "1_1") (pintype "passive"))
      (node (ref "LCD1") (pin "2") (pinfunction "MISO_2") (pintype "output"))
      (node (ref "U2") (pin "11") (pinfunction "(PD0/MISO/PCINT3)PB3_11") (pintype "bidirectional"))
    )
    (net (code "34") (name "/MOSI") (class "Default")
      (node (ref "ICSP") (pin "4") (pinfunction "4_4") (pintype "passive"))
      (node (ref "LCD1") (pin "4") (pinfunction "MOSI_4") (pintype "input"))
      (node (ref "U2") (pin "10") (pinfunction "(PDI/MOSI/PCINT2)PB2_10") (pintype "bidirectional"))
    )
    (net (code "35") (name "/MUXA") (class "Default")
      (node (ref "IC3(1)") (pin "10") (pinfunction "A_10") (pintype "input"))
      (node (ref "U2") (pin "36") (pinfunction "(ADC7/TDI)PF7_36") (pintype "bidirectional"))
    )
    (net (code "36") (name "/MUXB") (class "Default")
      (node (ref "IC3(1)") (pin "11") (pinfunction "B_11") (pintype "input"))
      (node (ref "U2") (pin "37") (pinfunction "(ADC6/TDO)PF6_37") (pintype "bidirectional"))
    )
    (net (code "37") (name "/MUXC") (class "Default")
      (node (ref "IC3(1)") (pin "14") (pinfunction "C_14") (pintype "input"))
      (node (ref "U2") (pin "38") (pinfunction "(ADC5/TMS)PF5_38") (pintype "bidirectional"))
    )
    (net (code "38") (name "/MUXD") (class "Default")
      (node (ref "IC3(1)") (pin "13") (pinfunction "D_13") (pintype "input"))
      (node (ref "U2") (pin "39") (pinfunction "(ADC4/TCK)PF4_39") (pintype "bidirectional"))
    )
    (net (code "39") (name "/OUT2") (class "Default")
      (node (ref "OUT2") (pin "2") (pinfunction "2_2") (pintype "passive"))
      (node (ref "U2") (pin "12") (pinfunction "(PCINT7/OC0A/OC1C/#RTS)PB7_12") (pintype "bidirectional"))
    )
    (net (code "40") (name "/OUT3") (class "Default")
      (node (ref "OUT3") (pin "2") (pinfunction "2_2") (pintype "passive"))
      (node (ref "U2") (pin "18") (pinfunction "(OC0B/SCL/INT0)PD0_18") (pintype "bidirectional"))
    )
    (net (code "41") (name "/RD+") (class "Default")
      (node (ref "RN2") (pin "2") (pinfunction "1_2") (pintype "passive"))
      (node (ref "U2") (pin "4") (pinfunction "D+_4") (pintype "bidirectional"))
    )
    (net (code "42") (name "/RD-") (class "Default")
      (node (ref "RN2") (pin "4") (pinfunction "1_4") (pintype "passive"))
      (node (ref "U2") (pin "3") (pinfunction "D-_3") (pintype "bidirectional"))
    )
    (net (code "43") (name "/RESET") (class "Default")
      (node (ref "ICSP") (pin "5") (pinfunction "5_5") (pintype "passive"))
      (node (ref "R7") (pin "2") (pinfunction "2_2") (pintype "passive"))
      (node (ref "TS42") (pin "1") (pinfunction "1_1") (pintype "passive"))
      (node (ref "TS42") (pin "2") (pinfunction "2_2") (pintype "passive"))
      (node (ref "U2") (pin "13") (pinfunction "RESET_13") (pintype "input"))
    )
    (net (code "44") (name "/RST_LCD") (class "Default")
      (node (ref "LCD1") (pin "8") (pinfunction "RESET_8") (pintype "input"))
      (node (ref "U2") (pin "21") (pinfunction "(TXD1/INT3)PD3_21") (pintype "bidirectional"))
    )
    (net (code "45") (name "/RXLED") (class "Default")
      (node (ref "RX") (pin "C") (pinfunction "C_C") (pintype "passive"))
      (node (ref "U2") (pin "8") (pinfunction "(SS/PCINT0)PB0_8") (pintype "bidirectional"))
    )
    (net (code "46") (name "/SCK") (class "Default")
      (node (ref "ICSP") (pin "3") (pinfunction "3_3") (pintype "passive"))
      (node (ref "LCD1") (pin "3") (pinfunction "SCK_3") (pintype "input"))
      (node (ref "U2") (pin "9") (pinfunction "(SCLK/PCINT1)PB1_9") (pintype "bidirectional"))
    )
    (net (code "47") (name "/TXLED") (class "Default")
      (node (ref "TX") (pin "C") (pinfunction "C_C") (pintype "passive"))
      (node (ref "U2") (pin "22") (pinfunction "(XCK1/#CTS)PD5_22") (pintype "bidirectional"))
    )
    (net (code "48") (name "/UCAP") (class "Default")
      (node (ref "C16") (pin "1") (pinfunction "1_1") (pintype "passive"))
      (node (ref "U2") (pin "6") (pinfunction "UCAP_6") (pintype "passive"))
    )
    (net (code "49") (name "/USBID") (class "Default")
      (node (ref "J1") (pin "P4") (pinfunction "ID_P4") (pintype "bidirectional"))
    )
    (net (code "50") (name "/USH") (class "Default")
      (node (ref "J1") (pin "P$1") (pinfunction "SH7_P$1") (pintype "passive"))
      (node (ref "J1") (pin "P$2") (pinfunction "SH8_P$2") (pintype "passive"))
      (node (ref "J1") (pin "P$3") (pinfunction "SH9_P$3") (pintype "passive"))
      (node (ref "J1") (pin "P$4") (pinfunction "SH10_P$4") (pintype "passive"))
      (node (ref "J1") (pin "P$5") (pinfunction "SH7_P$5") (pintype "passive"))
      (node (ref "J1") (pin "P$6") (pinfunction "SH8_P$6") (pintype "passive"))
      (node (ref "J1") (pin "P$7") (pinfunction "SH9_P$7") (pintype "passive"))
      (node (ref "J1") (pin "P$8") (pinfunction "SH10_P$8") (pintype "passive"))
      (node (ref "J1") (pin "S1") (pinfunction "SH1_S1") (pintype "passive"))
      (node (ref "J1") (pin "S2") (pinfunction "SH2_S2") (pintype "passive"))
      (node (ref "J1") (pin "S3") (pinfunction "SH3_S3") (pintype "passive"))
      (node (ref "J1") (pin "S4") (pinfunction "SH4_S4") (pintype "passive"))
      (node (ref "J1") (pin "S5") (pinfunction "SH5_S5") (pintype "passive"))
      (node (ref "J1") (pin "S6") (pinfunction "SH6_S6") (pintype "passive"))
      (node (ref "L2") (pin "2") (pinfunction "2_2") (pintype "passive"))
    )
    (net (code "51") (name "/XOUT") (class "Default")
      (node (ref "C21") (pin "2") (pinfunction "2_2") (pintype "passive"))
      (node (ref "IC4") (pin "2") (pinfunction "X-OUT_2") (pintype "output"))
      (node (ref "U2") (pin "41") (pinfunction "(ADC0)PF0_41") (pintype "bidirectional"))
    )
    (net (code "52") (name "/XTAL1") (class "Default")
      (node (ref "C11") (pin "1") (pinfunction "1_1") (pintype "passive"))
      (node (ref "R9") (pin "1") (pinfunction "1_1") (pintype "passive"))
      (node (ref "U2") (pin "17") (pinfunction "XTAL1_17") (pintype "bidirectional"))
      (node (ref "Y1") (pin "1") (pinfunction "C1_1") (pintype "passive"))
    )
    (net (code "53") (name "/XTAL2") (class "Default")
      (node (ref "C10") (pin "2") (pinfunction "2_2") (pintype "passive"))
      (node (ref "R9") (pin "2") (pinfunction "2_2") (pintype "passive"))
      (node (ref "U2") (pin "16") (pinfunction "XTAL2_16") (pintype "bidirectional"))
      (node (ref "Y1") (pin "3") (pinfunction "C2_3") (pintype "passive"))
    )
    (net (code "54") (name "/XUSB") (class "Default")
      (node (ref "F1") (pin "2") (pinfunction "2_2") (pintype "passive"))
      (node (ref "J1") (pin "P1") (pinfunction "VBUS_P1") (pintype "power_in"))
    )
    (net (code "55") (name "/YOUT") (class "Default")
      (node (ref "C20") (pin "2") (pinfunction "2_2") (pintype "passive"))
      (node (ref "IC4") (pin "3") (pinfunction "Y-OUT_3") (pintype "output"))
      (node (ref "U2") (pin "26") (pinfunction "(T1/#OC4D/ADC9)PD6_26") (pintype "bidirectional"))
    )
    (net (code "56") (name "/ZOUT") (class "Default")
      (node (ref "C19") (pin "2") (pinfunction "2_2") (pintype "passive"))
      (node (ref "IC4") (pin "4") (pinfunction "Z-OUT_4") (pintype "output"))
      (node (ref "U2") (pin "25") (pinfunction "(ICP1/ADC8)PD4_25") (pintype "bidirectional"))
    )
    (net (code "57") (name "GND") (class "Default")
      (node (ref "C10") (pin "1") (pinfunction "1_1") (pintype "passive"))
      (node (ref "C11") (pin "2") (pinfunction "2_2") (pintype "passive"))
      (node (ref "C12") (pin "1") (pinfunction "1_1") (pintype "passive"))
      (node (ref "C13") (pin "2") (pinfunction "2_2") (pintype "passive"))
      (node (ref "C14") (pin "2") (pinfunction "2_2") (pintype "passive"))
      (node (ref "C15") (pin "2") (pinfunction "2_2") (pintype "passive"))
      (node (ref "C16") (pin "2") (pinfunction "2_2") (pintype "passive"))
      (node (ref "C17") (pin "1") (pinfunction "1_1") (pintype "passive"))
      (node (ref "C18") (pin "1") (pinfunction "1_1") (pintype "passive"))
      (node (ref "C19") (pin "1") (pinfunction "1_1") (pintype "passive"))
      (node (ref "C2") (pin "1") (pinfunction "1_1") (pintype "passive"))
      (node (ref "C20") (pin "1") (pinfunction "1_1") (pintype "passive"))
      (node (ref "C21") (pin "1") (pinfunction "1_1") (pintype "passive"))
      (node (ref "C22") (pin "-") (pinfunction "-_-") (pintype "passive"))
      (node (ref "C23") (pin "-") (pinfunction "-_-") (pintype "passive"))
      (node (ref "C24") (pin "1") (pinfunction "1_1") (pintype "passive"))
      (node (ref "C25") (pin "1") (pinfunction "1_1") (pintype "passive"))
      (node (ref "C26") (pin "1") (pinfunction "1_1") (pintype "passive"))
      (node (ref "C27") (pin "1") (pinfunction "1_1") (pintype "passive"))
      (node (ref "C28") (pin "1") (pinfunction "1_1") (pintype "passive"))
      (node (ref "C29") (pin "1") (pinfunction "1_1") (pintype "passive"))
      (node (ref "C3") (pin "1") (pinfunction "1_1") (pintype "passive"))
      (node (ref "C30") (pin "2") (pinfunction "2_2") (pintype "passive"))
      (node (ref "C31") (pin "2") (pinfunction "2_2") (pintype "passive"))
      (node (ref "C33") (pin "1") (pinfunction "1_1") (pintype "passive"))
      (node (ref "C34") (pin "1") (pinfunction "1_1") (pintype "passive"))
      (node (ref "C4") (pin "1") (pinfunction "1_1") (pintype "passive"))
      (node (ref "C5") (pin "1") (pinfunction "1_1") (pintype "passive"))
      (node (ref "C6") (pin "1") (pinfunction "1_1") (pintype "passive"))
      (node (ref "C7") (pin "1") (pinfunction "1_1") (pintype "passive"))
      (node (ref "C8") (pin "1") (pinfunction "1_1") (pintype "passive"))
      (node (ref "C9") (pin "1") (pinfunction "1_1") (pintype "passive"))
      (node (ref "IC1") (pin "4") (pinfunction "V-_4") (pintype "power_in"))
      (node (ref "IC2") (pin "3") (pinfunction "GND_3") (pintype "power_in"))
      (node (ref "IC3(1)") (pin "12") (pinfunction "VSS_12") (pintype "power_in"))
      (node (ref "IC3(1)") (pin "15") (pinfunction "INH_15") (pintype "input"))
      (node (ref "IC3(1)") (pin "16") (pinfunction "X15_16") (pintype "input"))
      (node (ref "IC3(1)") (pin "17") (pinfunction "X14_17") (pintype "input"))
      (node (ref "IC3(1)") (pin "18") (pinfunction "X13_18") (pintype "input"))
      (node (ref "IC4") (pin "5") (pinfunction "VSS_5") (pintype "power_in"))
      (node (ref "ICSP") (pin "6") (pinfunction "6_6") (pintype "passive"))
      (node (ref "INA") (pin "1") (pinfunction "1_1") (pintype "passive"))
      (node (ref "INB") (pin "1") (pinfunction "1_1") (pintype "passive"))
      (node (ref "J1") (pin "P5") (pinfunction "GND_P5") (pintype "passive"))
      (node (ref "L") (pin "C") (pinfunction "C_C") (pintype "passive"))
      (node (ref "L2") (pin "1") (pinfunction "1_1") (pintype "passive"))
      (node (ref "LCD1") (pin "10") (pinfunction "GND_10") (pintype "power_in"))
      (node (ref "LED1") (pin "4") (pinfunction "BC_4") (pintype "passive"))
      (node (ref "LED1") (pin "5") (pinfunction "GC_5") (pintype "passive"))
      (node (ref "LED1") (pin "6") (pinfunction "RC_6") (pintype "passive"))
      (node (ref "LINEAR") (pin "3") (pinfunction "3_3") (pintype "bidirectional"))
      (node (ref "LINEAR") (pin "CHASSIS1") (pinfunction "CHASSIS-GND-1_CHASSIS1") (pintype "bidirectional"))
      (node (ref "LINEAR") (pin "CHASSIS2") (pinfunction "CHASSIS-GND-2_CHASSIS2") (pintype "bidirectional"))
      (node (ref "LINEAR") (pin "CHASSIS3") (pinfunction "CHASSIS-GND-3_CHASSIS3") (pintype "bidirectional"))
      (node (ref "LINEAR") (pin "CHASSIS4") (pinfunction "CHASSIS-GND-4_CHASSIS4") (pintype "bidirectional"))
      (node (ref "MIC1") (pin "2") (pinfunction "2_2") (pintype "passive"))
      (node (ref "ON") (pin "C") (pinfunction "C_C") (pintype "passive"))
      (node (ref "OUT2") (pin "1") (pinfunction "1_1") (pintype "passive"))
      (node (ref "OUT3") (pin "1") (pinfunction "1_1") (pintype "passive"))
      (node (ref "P1") (pin "B2A") (pinfunction "SEL-_B2A") (pintype "bidirectional"))
      (node (ref "P1") (pin "H3") (pinfunction "H-_H3") (pintype "bidirectional"))
      (node (ref "P1") (pin "V3") (pinfunction "V-_V3") (pintype "bidirectional"))
      (node (ref "R10") (pin "2") (pinfunction "2_2") (pintype "passive"))
      (node (ref "R11") (pin "2") (pinfunction "2_2") (pintype "passive"))
      (node (ref "R13") (pin "1") (pinfunction "1_1") (pintype "passive"))
      (node (ref "R18") (pin "2") (pinfunction "2_2") (pintype "passive"))
      (node (ref "R3") (pin "2") (pinfunction "2_2") (pintype "passive"))
      (node (ref "R4") (pin "2") (pinfunction "2_2") (pintype "passive"))
      (node (ref "R5") (pin "2") (pinfunction "2_2") (pintype "passive"))
      (node (ref "R6") (pin "2") (pinfunction "2_2") (pintype "passive"))
      (node (ref "RN1") (pin "8") (pinfunction "2_8") (pintype "passive"))
      (node (ref "RN2") (pin "1") (pinfunction "1_1") (pintype "passive"))
      (node (ref "RN2") (pin "8") (pinfunction "2_8") (pintype "passive"))
      (node (ref "S1") (pin "P$1") (pinfunction "1_P$1") (pintype "passive"))
      (node (ref "S1") (pin "P$2") (pinfunction "2_P$2") (pintype "passive"))
      (node (ref "S2") (pin "P$3") (pinfunction "3_P$3") (pintype "passive"))
      (node (ref "S2") (pin "P$4") (pinfunction "4_P$4") (pintype "passive"))
      (node (ref "S3") (pin "P$1") (pinfunction "1_P$1") (pintype "passive"))
      (node (ref "S3") (pin "P$2") (pinfunction "2_P$2") (pintype "passive"))
      (node (ref "S4") (pin "P$1") (pinfunction "1_P$1") (pintype "passive"))
      (node (ref "S4") (pin "P$2") (pinfunction "2_P$2") (pintype "passive"))
      (node (ref "SJ1") (pin "3") (pinfunction "3_3") (pintype "passive"))
      (node (ref "SJ2") (pin "3") (pinfunction "3_3") (pintype "passive"))
      (node (ref "T1") (pin "2") (pinfunction "E_2") (pintype "passive"))
      (node (ref "TS42") (pin "3") (pinfunction "3_3") (pintype "passive"))
      (node (ref "TS42") (pin "4") (pinfunction "4_4") (pintype "passive"))
      (node (ref "U2") (pin "15") (pinfunction "GND_15") (pintype "power_in"))
      (node (ref "U2") (pin "23") (pinfunction "GND1_23") (pintype "power_in"))
      (node (ref "U2") (pin "35") (pinfunction "GND2_35") (pintype "power_in"))
      (node (ref "U2") (pin "43") (pinfunction "GND3_43") (pintype "power_in"))
      (node (ref "U2") (pin "5") (pinfunction "UGND_5") (pintype "power_in"))
      (node (ref "U2") (pin "EXP") (pinfunction "PAD_EXP") (pintype "power_in"))
      (node (ref "U4") (pin "2") (pinfunction "GND_2") (pintype "power_in"))
      (node (ref "Y1") (pin "2") (pinfunction "GND_2") (pintype "passive"))
      (node (ref "Y1") (pin "4") (pinfunction "GND_4") (pintype "passive"))
      (node (ref "Z1") (pin "2") (pinfunction "2_2") (pintype "passive"))
      (node (ref "Z2") (pin "2") (pinfunction "2_2") (pintype "passive"))
    )
    (net (code "58") (name "Net-(C35-Pad1)") (class "Default")
      (node (ref "C35") (pin "1") (pinfunction "1_1") (pintype "passive"))
      (node (ref "MIC1") (pin "1") (pinfunction "1_1") (pintype "passive"))
      (node (ref "R2") (pin "2") (pinfunction "2_2") (pintype "passive"))
    )
    (net (code "59") (name "Net-(IC1A-+IN)") (class "Default")
      (node (ref "IC1") (pin "3") (pinfunction "+IN_3") (pintype "input"))
      (node (ref "IC1") (pin "7") (pinfunction "OUT_7") (pintype "output"))
      (node (ref "R1") (pin "2") (pinfunction "2_2") (pintype "passive"))
    )
    (net (code "60") (name "Net-(IC1A--IN)") (class "Default")
      (node (ref "D1") (pin "A") (pinfunction "A_A") (pintype "passive"))
      (node (ref "IC1") (pin "1") (pinfunction "OUT_1") (pintype "output"))
      (node (ref "IC1") (pin "2") (pinfunction "-IN_2") (pintype "input"))
    )
    (net (code "61") (name "Net-(IC1B-+IN)") (class "Default")
      (node (ref "C35") (pin "2") (pinfunction "2_2") (pintype "passive"))
      (node (ref "IC1") (pin "5") (pinfunction "+IN_5") (pintype "input"))
      (node (ref "R4") (pin "1") (pinfunction "1_1") (pintype "passive"))
    )
    (net (code "62") (name "Net-(IC1B--IN)") (class "Default")
      (node (ref "IC1") (pin "6") (pinfunction "-IN_6") (pintype "input"))
      (node (ref "R1") (pin "1") (pinfunction "1_1") (pintype "passive"))
      (node (ref "R5") (pin "1") (pinfunction "1_1") (pintype "passive"))
    )
    (net (code "63") (name "Net-(IC4-S-TEST)") (class "Default")
      (node (ref "IC4") (pin "13") (pinfunction "S-TEST_13") (pintype "input"))
      (node (ref "R13") (pin "2") (pinfunction "2_2") (pintype "passive"))
      (node (ref "SJ2") (pin "2") (pinfunction "2_2") (pintype "passive"))
    )
    (net (code "64") (name "Net-(LED1-BA)") (class "Default")
      (node (ref "LED1") (pin "3") (pinfunction "BA_3") (pintype "passive"))
      (node (ref "RN1") (pin "5") (pinfunction "2_5") (pintype "passive"))
    )
    (net (code "65") (name "Net-(LED1-GA)") (class "Default")
      (node (ref "LED1") (pin "2") (pinfunction "GA_2") (pintype "passive"))
      (node (ref "RN1") (pin "6") (pinfunction "2_6") (pintype "passive"))
    )
    (net (code "66") (name "Net-(LED1-RA)") (class "Default")
      (node (ref "LED1") (pin "1") (pinfunction "RA_1") (pintype "passive"))
      (node (ref "RN1") (pin "7") (pinfunction "2_7") (pintype "passive"))
    )
    (net (code "67") (name "Net-(PH1(1)-Pad1)") (class "Default")
      (node (ref "PH1(1)") (pin "1") (pinfunction "1_1") (pintype "passive"))
      (node (ref "PH1(2)") (pin "1") (pinfunction "1_1") (pintype "passive"))
      (node (ref "PH1(3)") (pin "1") (pinfunction "1_1") (pintype "bidirectional"))
      (node (ref "R8") (pin "2") (pinfunction "2_2") (pintype "passive"))
    )
    (net (code "68") (name "Net-(RN3A-2)") (class "Default")
      (node (ref "ON") (pin "A") (pinfunction "A_A") (pintype "passive"))
      (node (ref "RN3") (pin "8") (pinfunction "2_8") (pintype "passive"))
    )
    (net (code "69") (name "Net-(RN3B-2)") (class "Default")
      (node (ref "L") (pin "A") (pinfunction "A_A") (pintype "passive"))
      (node (ref "RN3") (pin "7") (pinfunction "2_7") (pintype "passive"))
    )
    (net (code "70") (name "Net-(RN3C-2)") (class "Default")
      (node (ref "RN3") (pin "6") (pinfunction "2_6") (pintype "passive"))
      (node (ref "TX") (pin "A") (pinfunction "A_A") (pintype "passive"))
    )
    (net (code "71") (name "Net-(RN3D-2)") (class "Default")
      (node (ref "RN3") (pin "5") (pinfunction "2_5") (pintype "passive"))
      (node (ref "RX") (pin "A") (pinfunction "A_A") (pintype "passive"))
    )
    (net (code "72") (name "Net-(T1-B)") (class "Default")
      (node (ref "R12") (pin "1") (pinfunction "1_1") (pintype "passive"))
      (node (ref "T1") (pin "1") (pinfunction "B_1") (pintype "passive"))
    )
    (net (code "73") (name "Net-(T1-C)") (class "Default")
      (node (ref "R15") (pin "2") (pinfunction "2_2") (pintype "passive"))
      (node (ref "T1") (pin "3") (pinfunction "C_3") (pintype "passive"))
    )
    (net (code "74") (name "unconnected-(IC4-0G-DET-Pad9)") (class "Default")
      (node (ref "IC4") (pin "9") (pinfunction "0G-DET_9") (pintype "output"))
    )
    (net (code "75") (name "unconnected-(IC4-NC-Pad1)") (class "Default")
      (node (ref "IC4") (pin "1") (pinfunction "NC_1") (pintype "no_connect"))
    )
    (net (code "76") (name "unconnected-(IC4-NC-Pad8)") (class "Default")
      (node (ref "IC4") (pin "8") (pinfunction "NC_8") (pintype "no_connect"))
    )
    (net (code "77") (name "unconnected-(IC4-NC-Pad11)") (class "Default")
      (node (ref "IC4") (pin "11") (pinfunction "NC_11") (pintype "no_connect"))
    )
    (net (code "78") (name "unconnected-(IC4-NC-Pad12)") (class "Default")
      (node (ref "IC4") (pin "12") (pinfunction "NC_12") (pintype "no_connect"))
    )
    (net (code "79") (name "unconnected-(IC4-NC-Pad14)") (class "Default")
      (node (ref "IC4") (pin "14") (pinfunction "NC_14") (pintype "no_connect"))
    )
    (net (code "80") (name "unconnected-(RN2C-1-Pad3)") (class "Default")
      (node (ref "RN2") (pin "3") (pinfunction "1_3") (pintype "passive"))
    )
    (net (code "81") (name "unconnected-(RN2C-2-Pad6)") (class "Default")
      (node (ref "RN2") (pin "6") (pinfunction "2_6") (pintype "passive"))
    )
    (net (code "82") (name "unconnected-(U2-(SDA{slash}INT1)PD1-Pad19)") (class "Default")
      (node (ref "U2") (pin "19") (pinfunction "(SDA/INT1)PD1_19") (pintype "bidirectional"))
    )
    (net (code "83") (name "unconnected-(U4-NC{slash}FB-Pad4)") (class "Default")
      (node (ref "U4") (pin "4") (pinfunction "NC/FB_4") (pintype "passive"))
    )
  )
)
